# PureRingMod.net
KiCad netlist of a schematic drawn in EAGLE
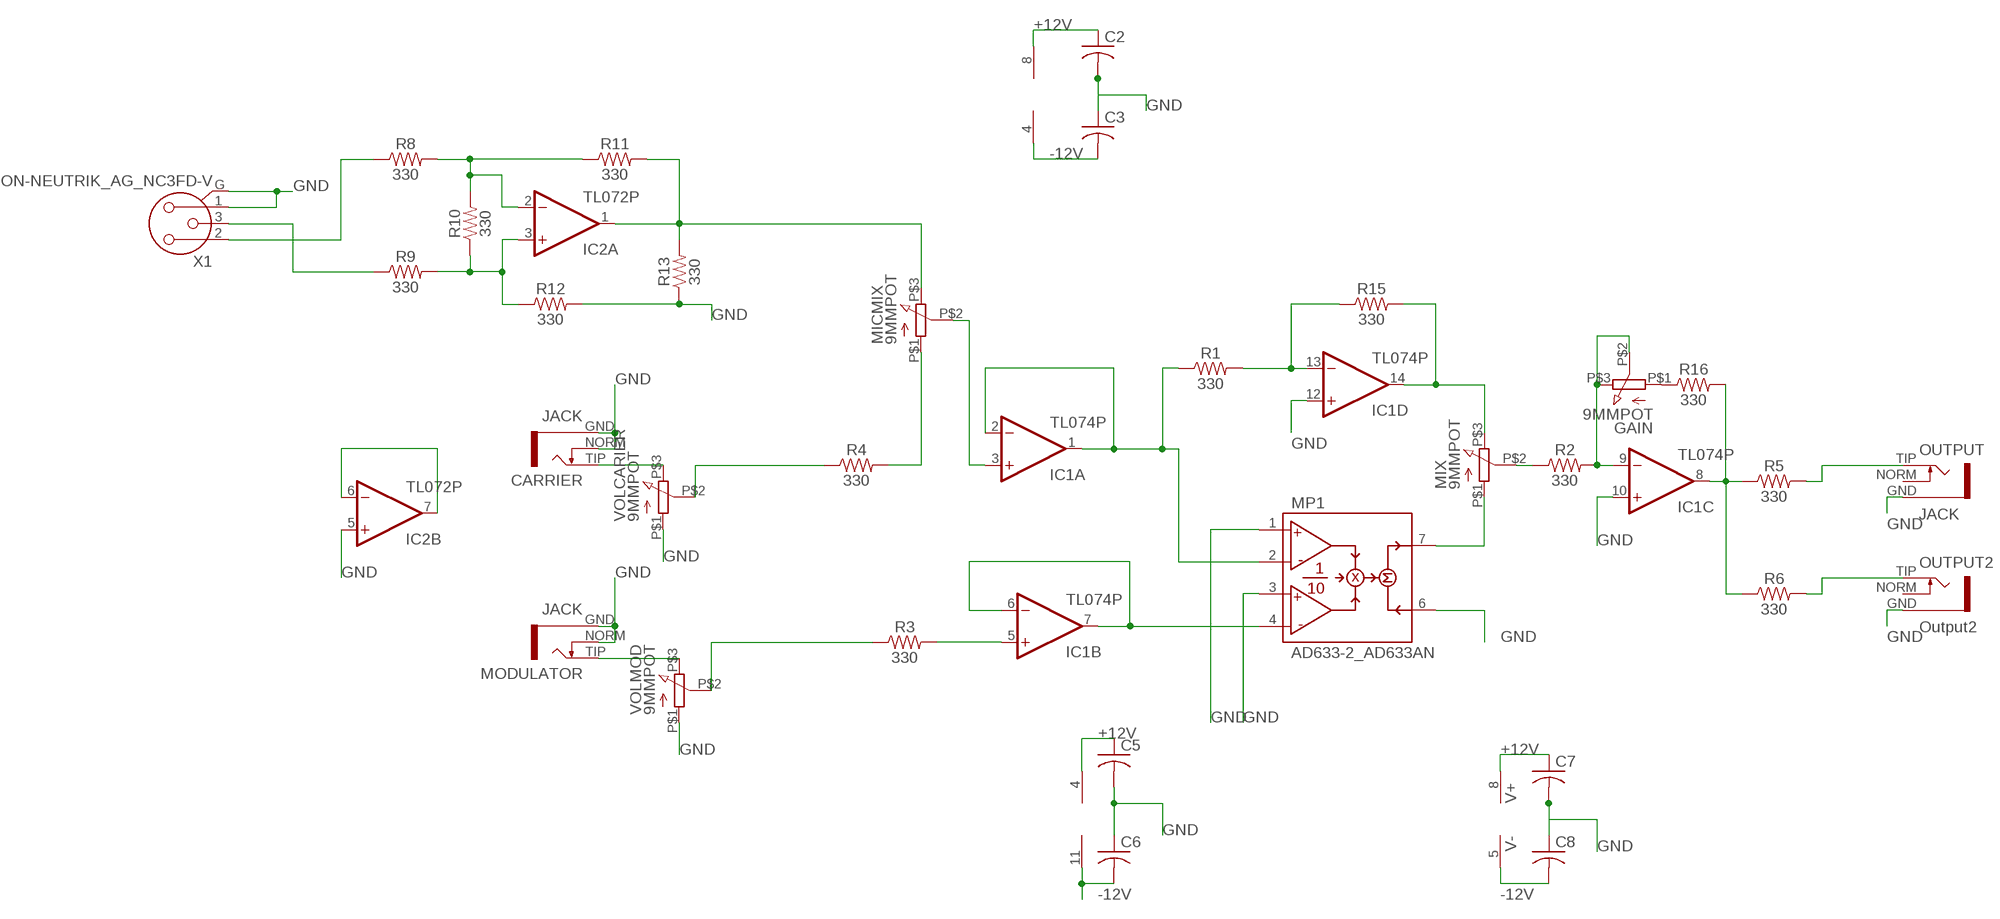
[diagram p0: schematic, sheet 1]
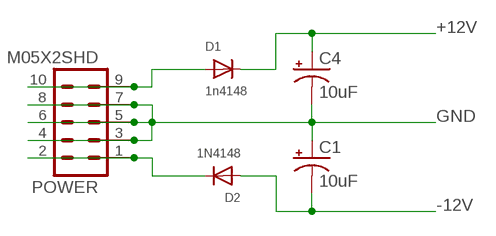
[diagram p1: schematic, sheet 2]

(export (version "E")
  (design (tool "Eeschema 10.0.6"))
  (components
    (comp (ref "C1")
      (value "10uF")
      (footprint "eagle-import:CPOL-RADIAL-2.5MM-5MM")
      (libsource (lib "eagle-import") (part "10UF-POLAR-RADIAL-2.5MM-25V-20%"))
    )
    (comp (ref "C4")
      (value "10uF")
      (footprint "eagle-import:CPOL-RADIAL-2.5MM-5MM")
      (libsource (lib "eagle-import") (part "10UF-POLAR-RADIAL-2.5MM-25V-20%"))
    )
    (comp (ref "D1")
      (value "1n4148")
      (footprint "eagle-import:DO-1N4148")
      (libsource (lib "eagle-import") (part "DIODEDO-1N4148"))
    )
    (comp (ref "D2")
      (value "1N4148")
      (footprint "eagle-import:DO-1N4148")
      (libsource (lib "eagle-import") (part "DIODEDO-1N4148"))
    )
    (comp (ref "POWER")
      (value "M05X2SHD")
      (footprint "eagle-import:2X5-SHROUDED")
      (libsource (lib "eagle-import") (part "M05X2SHD"))
    )
    (comp (ref "C2")
      (value "CAPACITOR-US050-025X075")
      (footprint "eagle-import:C050-025X075")
      (libsource (lib "eagle-import") (part "CAPACITOR-US050-025X075"))
    )
    (comp (ref "C3")
      (value "CAPACITOR-US050-025X075")
      (footprint "eagle-import:C050-025X075")
      (libsource (lib "eagle-import") (part "CAPACITOR-US050-025X075"))
    )
    (comp (ref "C5")
      (value "CAPACITOR-US050-025X075")
      (footprint "eagle-import:C050-025X075")
      (libsource (lib "eagle-import") (part "CAPACITOR-US050-025X075"))
    )
    (comp (ref "C6")
      (value "CAPACITOR-US050-025X075")
      (footprint "eagle-import:C050-025X075")
      (libsource (lib "eagle-import") (part "CAPACITOR-US050-025X075"))
    )
    (comp (ref "C7")
      (value "CAPACITOR-US050-025X075")
      (footprint "eagle-import:C050-025X075")
      (libsource (lib "eagle-import") (part "CAPACITOR-US050-025X075"))
    )
    (comp (ref "C8")
      (value "CAPACITOR-US050-025X075")
      (footprint "eagle-import:C050-025X075")
      (libsource (lib "eagle-import") (part "CAPACITOR-US050-025X075"))
    )
    (comp (ref "CARRIER")
      (value "JACK")
      (footprint "eagle-import:JACK")
      (libsource (lib "eagle-import") (part "JACK"))
    )
    (comp (ref "GAIN")
      (value "9MMPOT")
      (footprint "eagle-import:POT")
      (libsource (lib "eagle-import") (part "9MMPOT"))
    )
    (comp (ref "IC1")
      (value "TL074P")
      (footprint "eagle-import:DIL14")
      (libsource (lib "eagle-import") (part "TL074P"))
    )
    (comp (ref "IC2")
      (value "TL072P")
      (footprint "eagle-import:DIL08")
      (libsource (lib "eagle-import") (part "TL072P"))
    )
    (comp (ref "MICMIX")
      (value "9MMPOT")
      (footprint "eagle-import:POT")
      (libsource (lib "eagle-import") (part "9MMPOT"))
    )
    (comp (ref "MIX")
      (value "9MMPOT")
      (footprint "eagle-import:POT")
      (libsource (lib "eagle-import") (part "9MMPOT"))
    )
    (comp (ref "MODULATOR")
      (value "JACK")
      (footprint "eagle-import:JACK")
      (libsource (lib "eagle-import") (part "JACK"))
    )
    (comp (ref "MP1")
      (value "AD633-2_AD633AN")
      (footprint "eagle-import:AD633-2_DIL08")
      (libsource (lib "eagle-import") (part "AD633-2_AD633NA"))
    )
    (comp (ref "OUTPUT")
      (value "JACK")
      (footprint "eagle-import:JACK")
      (libsource (lib "eagle-import") (part "JACK"))
    )
    (comp (ref "OUTPUT2")
      (value "Output2")
      (footprint "eagle-import:JACK")
      (libsource (lib "eagle-import") (part "JACK"))
    )
    (comp (ref "R1")
      (value "330")
      (footprint "eagle-import:AXIAL-0.3")
      (libsource (lib "eagle-import") (part "330OHM-HORIZ-1/10W-5%"))
    )
    (comp (ref "R2")
      (value "330")
      (footprint "eagle-import:AXIAL-0.3")
      (libsource (lib "eagle-import") (part "330OHM-HORIZ-1/10W-5%"))
    )
    (comp (ref "R3")
      (value "330")
      (footprint "eagle-import:AXIAL-0.3")
      (libsource (lib "eagle-import") (part "330OHM-HORIZ-1/10W-5%"))
    )
    (comp (ref "R4")
      (value "330")
      (footprint "eagle-import:AXIAL-0.3")
      (libsource (lib "eagle-import") (part "330OHM-HORIZ-1/10W-5%"))
    )
    (comp (ref "R5")
      (value "330")
      (footprint "eagle-import:AXIAL-0.3")
      (libsource (lib "eagle-import") (part "330OHM-HORIZ-1/10W-5%"))
    )
    (comp (ref "R6")
      (value "330")
      (footprint "eagle-import:AXIAL-0.3")
      (libsource (lib "eagle-import") (part "330OHM-HORIZ-1/10W-5%"))
    )
    (comp (ref "R8")
      (value "330")
      (footprint "eagle-import:AXIAL-0.3")
      (libsource (lib "eagle-import") (part "330OHM-HORIZ-1/10W-5%"))
    )
    (comp (ref "R9")
      (value "330")
      (footprint "eagle-import:AXIAL-0.3")
      (libsource (lib "eagle-import") (part "330OHM-HORIZ-1/10W-5%"))
    )
    (comp (ref "R10")
      (value "330")
      (footprint "eagle-import:AXIAL-0.3")
      (libsource (lib "eagle-import") (part "330OHM-HORIZ-1/10W-5%"))
    )
    (comp (ref "R11")
      (value "330")
      (footprint "eagle-import:AXIAL-0.3")
      (libsource (lib "eagle-import") (part "330OHM-HORIZ-1/10W-5%"))
    )
    (comp (ref "R12")
      (value "330")
      (footprint "eagle-import:AXIAL-0.3")
      (libsource (lib "eagle-import") (part "330OHM-HORIZ-1/10W-5%"))
    )
    (comp (ref "R13")
      (value "330")
      (footprint "eagle-import:AXIAL-0.3")
      (libsource (lib "eagle-import") (part "330OHM-HORIZ-1/10W-5%"))
    )
    (comp (ref "R15")
      (value "330")
      (footprint "eagle-import:AXIAL-0.3")
      (libsource (lib "eagle-import") (part "330OHM-HORIZ-1/10W-5%"))
    )
    (comp (ref "R16")
      (value "330")
      (footprint "eagle-import:AXIAL-0.3")
      (libsource (lib "eagle-import") (part "330OHM-HORIZ-1/10W-5%"))
    )
    (comp (ref "VOLCARIER")
      (value "9MMPOT")
      (footprint "eagle-import:POT")
      (libsource (lib "eagle-import") (part "9MMPOT"))
    )
    (comp (ref "VOLMOD")
      (value "9MMPOT")
      (footprint "eagle-import:POT")
      (libsource (lib "eagle-import") (part "9MMPOT"))
    )
    (comp (ref "X1")
      (value "CON-NEUTRIK_AG_NC3FD-V")
      (footprint "eagle-import:CON-NEUTRIK_AG_NC3FD-V")
      (fields (field (name "MF") "FARNELL") (field (name "MPN") "NC3FDV") (field (name "RS-PART") "448-244"))
      (libsource (lib "eagle-import") (part "CON-NEUTRIK_AG_NC3FD-V"))
    )
  )
  (nets
    (net (code "1") (name "+12V") (class "Default")
      (node (ref "C2") (pin "1") (pinfunction "1_1") (pintype "passive"))
      (node (ref "C4") (pin "1") (pinfunction "+_1") (pintype "passive"))
      (node (ref "C5") (pin "1") (pinfunction "1_1") (pintype "passive"))
      (node (ref "C7") (pin "1") (pinfunction "1_1") (pintype "passive"))
      (node (ref "D1") (pin "C") (pinfunction "C_C") (pintype "passive"))
      (node (ref "IC1") (pin "4") (pinfunction "V+_4") (pintype "power_in"))
      (node (ref "IC2") (pin "8") (pinfunction "V+_8") (pintype "power_in"))
      (node (ref "MP1") (pin "8") (pinfunction "V+_8") (pintype "power_in"))
    )
    (net (code "2") (name "-12V") (class "Default")
      (node (ref "C1") (pin "2") (pinfunction "-_2") (pintype "passive"))
      (node (ref "C3") (pin "2") (pinfunction "2_2") (pintype "passive"))
      (node (ref "C6") (pin "2") (pinfunction "2_2") (pintype "passive"))
      (node (ref "C8") (pin "2") (pinfunction "2_2") (pintype "passive"))
      (node (ref "D2") (pin "A") (pinfunction "A_A") (pintype "passive"))
      (node (ref "IC1") (pin "11") (pinfunction "V-_11") (pintype "power_in"))
      (node (ref "IC2") (pin "4") (pinfunction "V-_4") (pintype "power_in"))
      (node (ref "MP1") (pin "5") (pinfunction "V-_5") (pintype "power_in"))
    )
    (net (code "3") (name "GND") (class "Default")
      (node (ref "C1") (pin "1") (pinfunction "+_1") (pintype "passive"))
      (node (ref "C2") (pin "2") (pinfunction "2_2") (pintype "passive"))
      (node (ref "C3") (pin "1") (pinfunction "1_1") (pintype "passive"))
      (node (ref "C4") (pin "2") (pinfunction "-_2") (pintype "passive"))
      (node (ref "C5") (pin "2") (pinfunction "2_2") (pintype "passive"))
      (node (ref "C6") (pin "1") (pinfunction "1_1") (pintype "passive"))
      (node (ref "C7") (pin "2") (pinfunction "2_2") (pintype "passive"))
      (node (ref "C8") (pin "1") (pinfunction "1_1") (pintype "passive"))
      (node (ref "CARRIER") (pin "GND") (pinfunction "GND_GND") (pintype "passive"))
      (node (ref "CARRIER") (pin "NORM") (pinfunction "NORM_NORM") (pintype "passive"))
      (node (ref "IC1") (pin "10") (pinfunction "+IN_10") (pintype "input"))
      (node (ref "IC1") (pin "12") (pinfunction "+IN_12") (pintype "input"))
      (node (ref "IC2") (pin "5") (pinfunction "+IN_5") (pintype "input"))
      (node (ref "MODULATOR") (pin "GND") (pinfunction "GND_GND") (pintype "passive"))
      (node (ref "MODULATOR") (pin "NORM") (pinfunction "NORM_NORM") (pintype "passive"))
      (node (ref "MP1") (pin "1") (pinfunction "X1_1") (pintype "input"))
      (node (ref "MP1") (pin "3") (pinfunction "Y1_3") (pintype "input"))
      (node (ref "MP1") (pin "6") (pinfunction "Z_6") (pintype "input"))
      (node (ref "OUTPUT") (pin "GND") (pinfunction "GND_GND") (pintype "passive"))
      (node (ref "OUTPUT2") (pin "GND") (pinfunction "GND_GND") (pintype "passive"))
      (node (ref "POWER") (pin "3") (pinfunction "3_3") (pintype "passive"))
      (node (ref "POWER") (pin "4") (pinfunction "4_4") (pintype "passive"))
      (node (ref "POWER") (pin "5") (pinfunction "5_5") (pintype "passive"))
      (node (ref "POWER") (pin "6") (pinfunction "6_6") (pintype "passive"))
      (node (ref "POWER") (pin "7") (pinfunction "7_7") (pintype "passive"))
      (node (ref "POWER") (pin "8") (pinfunction "8_8") (pintype "passive"))
      (node (ref "R12") (pin "P$2") (pinfunction "2_P$2") (pintype "passive"))
      (node (ref "R13") (pin "P$1") (pinfunction "1_P$1") (pintype "passive"))
      (node (ref "VOLCARIER") (pin "P$1") (pinfunction "1_P$1") (pintype "passive"))
      (node (ref "VOLMOD") (pin "P$1") (pinfunction "1_P$1") (pintype "passive"))
      (node (ref "X1") (pin "1") (pinfunction "2_1") (pintype "passive"))
      (node (ref "X1") (pin "G") (pinfunction "G_G") (pintype "passive"))
    )
    (net (code "4") (name "Net-(D1-PadA)") (class "Default")
      (node (ref "D1") (pin "A") (pinfunction "A_A") (pintype "passive"))
      (node (ref "POWER") (pin "10") (pinfunction "10_10") (pintype "passive"))
      (node (ref "POWER") (pin "9") (pinfunction "9_9") (pintype "passive"))
    )
    (net (code "5") (name "Net-(D2-PadC)") (class "Default")
      (node (ref "D2") (pin "C") (pinfunction "C_C") (pintype "passive"))
      (node (ref "POWER") (pin "1") (pinfunction "1_1") (pintype "passive"))
      (node (ref "POWER") (pin "2") (pinfunction "2_2") (pintype "passive"))
    )
    (net (code "6") (name "Net-(GAIN-1)") (class "Default")
      (node (ref "GAIN") (pin "P$1") (pinfunction "1_P$1") (pintype "passive"))
      (node (ref "R16") (pin "P$1") (pinfunction "1_P$1") (pintype "passive"))
    )
    (net (code "7") (name "Net-(GAIN-2)") (class "Default")
      (node (ref "GAIN") (pin "P$2") (pinfunction "2_P$2") (pintype "passive"))
      (node (ref "GAIN") (pin "P$3") (pinfunction "3_P$3") (pintype "passive"))
      (node (ref "IC1") (pin "9") (pinfunction "-IN_9") (pintype "input"))
      (node (ref "R2") (pin "P$2") (pinfunction "2_P$2") (pintype "passive"))
    )
    (net (code "8") (name "Net-(IC1A-+IN)") (class "Default")
      (node (ref "IC1") (pin "3") (pinfunction "+IN_3") (pintype "input"))
      (node (ref "MICMIX") (pin "P$2") (pinfunction "2_P$2") (pintype "passive"))
    )
    (net (code "9") (name "Net-(IC1A--IN)") (class "Default")
      (node (ref "IC1") (pin "1") (pinfunction "OUT_1") (pintype "output"))
      (node (ref "IC1") (pin "2") (pinfunction "-IN_2") (pintype "input"))
      (node (ref "MP1") (pin "2") (pinfunction "X2_2") (pintype "input"))
      (node (ref "R1") (pin "P$1") (pinfunction "1_P$1") (pintype "passive"))
    )
    (net (code "10") (name "Net-(IC1B-+IN)") (class "Default")
      (node (ref "IC1") (pin "5") (pinfunction "+IN_5") (pintype "input"))
      (node (ref "R3") (pin "P$2") (pinfunction "2_P$2") (pintype "passive"))
    )
    (net (code "11") (name "Net-(IC1B--IN)") (class "Default")
      (node (ref "IC1") (pin "6") (pinfunction "-IN_6") (pintype "input"))
      (node (ref "IC1") (pin "7") (pinfunction "OUT_7") (pintype "output"))
      (node (ref "MP1") (pin "4") (pinfunction "Y2_4") (pintype "input"))
    )
    (net (code "12") (name "Net-(IC1C-OUT)") (class "Default")
      (node (ref "IC1") (pin "8") (pinfunction "OUT_8") (pintype "output"))
      (node (ref "R16") (pin "P$2") (pinfunction "2_P$2") (pintype "passive"))
      (node (ref "R5") (pin "P$1") (pinfunction "1_P$1") (pintype "passive"))
      (node (ref "R6") (pin "P$1") (pinfunction "1_P$1") (pintype "passive"))
    )
    (net (code "13") (name "Net-(IC1D--IN)") (class "Default")
      (node (ref "IC1") (pin "13") (pinfunction "-IN_13") (pintype "input"))
      (node (ref "R1") (pin "P$2") (pinfunction "2_P$2") (pintype "passive"))
      (node (ref "R15") (pin "P$1") (pinfunction "1_P$1") (pintype "passive"))
    )
    (net (code "14") (name "Net-(IC1D-OUT)") (class "Default")
      (node (ref "IC1") (pin "14") (pinfunction "OUT_14") (pintype "output"))
      (node (ref "MIX") (pin "P$3") (pinfunction "3_P$3") (pintype "passive"))
      (node (ref "R15") (pin "P$2") (pinfunction "2_P$2") (pintype "passive"))
    )
    (net (code "15") (name "Net-(IC2A-+IN)") (class "Default")
      (node (ref "IC2") (pin "3") (pinfunction "+IN_3") (pintype "input"))
      (node (ref "R10") (pin "P$1") (pinfunction "1_P$1") (pintype "passive"))
      (node (ref "R12") (pin "P$1") (pinfunction "1_P$1") (pintype "passive"))
      (node (ref "R9") (pin "P$2") (pinfunction "2_P$2") (pintype "passive"))
    )
    (net (code "16") (name "Net-(IC2A--IN)") (class "Default")
      (node (ref "IC2") (pin "2") (pinfunction "-IN_2") (pintype "input"))
      (node (ref "R10") (pin "P$2") (pinfunction "2_P$2") (pintype "passive"))
      (node (ref "R11") (pin "P$1") (pinfunction "1_P$1") (pintype "passive"))
      (node (ref "R8") (pin "P$2") (pinfunction "2_P$2") (pintype "passive"))
    )
    (net (code "17") (name "Net-(IC2A-OUT)") (class "Default")
      (node (ref "IC2") (pin "1") (pinfunction "OUT_1") (pintype "output"))
      (node (ref "MICMIX") (pin "P$3") (pinfunction "3_P$3") (pintype "passive"))
      (node (ref "R11") (pin "P$2") (pinfunction "2_P$2") (pintype "passive"))
      (node (ref "R13") (pin "P$2") (pinfunction "2_P$2") (pintype "passive"))
    )
    (net (code "18") (name "Net-(IC2B--IN)") (class "Default")
      (node (ref "IC2") (pin "6") (pinfunction "-IN_6") (pintype "input"))
      (node (ref "IC2") (pin "7") (pinfunction "OUT_7") (pintype "output"))
    )
    (net (code "19") (name "Net-(MICMIX-1)") (class "Default")
      (node (ref "MICMIX") (pin "P$1") (pinfunction "1_P$1") (pintype "passive"))
      (node (ref "R4") (pin "P$2") (pinfunction "2_P$2") (pintype "passive"))
    )
    (net (code "20") (name "Net-(MIX-1)") (class "Default")
      (node (ref "MIX") (pin "P$1") (pinfunction "1_P$1") (pintype "passive"))
      (node (ref "MP1") (pin "7") (pinfunction "W_7") (pintype "output"))
    )
    (net (code "21") (name "Net-(MIX-2)") (class "Default")
      (node (ref "MIX") (pin "P$2") (pinfunction "2_P$2") (pintype "passive"))
      (node (ref "R2") (pin "P$1") (pinfunction "1_P$1") (pintype "passive"))
    )
    (net (code "22") (name "Net-(R3-1)") (class "Default")
      (node (ref "R3") (pin "P$1") (pinfunction "1_P$1") (pintype "passive"))
      (node (ref "VOLMOD") (pin "P$2") (pinfunction "2_P$2") (pintype "passive"))
    )
    (net (code "23") (name "Net-(R4-1)") (class "Default")
      (node (ref "R4") (pin "P$1") (pinfunction "1_P$1") (pintype "passive"))
      (node (ref "VOLCARIER") (pin "P$2") (pinfunction "2_P$2") (pintype "passive"))
    )
    (net (code "24") (name "Net-(R5-2)") (class "Default")
      (node (ref "OUTPUT") (pin "TIP") (pinfunction "TIP_TIP") (pintype "passive"))
      (node (ref "R5") (pin "P$2") (pinfunction "2_P$2") (pintype "passive"))
    )
    (net (code "25") (name "Net-(R6-2)") (class "Default")
      (node (ref "OUTPUT2") (pin "TIP") (pinfunction "TIP_TIP") (pintype "passive"))
      (node (ref "R6") (pin "P$2") (pinfunction "2_P$2") (pintype "passive"))
    )
    (net (code "26") (name "Net-(R8-1)") (class "Default")
      (node (ref "R8") (pin "P$1") (pinfunction "1_P$1") (pintype "passive"))
      (node (ref "X1") (pin "2") (pinfunction "1_2") (pintype "passive"))
    )
    (net (code "27") (name "Net-(R9-1)") (class "Default")
      (node (ref "R9") (pin "P$1") (pinfunction "1_P$1") (pintype "passive"))
      (node (ref "X1") (pin "3") (pinfunction "3_3") (pintype "passive"))
    )
    (net (code "28") (name "Net-(VOLCARIER-3)") (class "Default")
      (node (ref "CARRIER") (pin "TIP") (pinfunction "TIP_TIP") (pintype "passive"))
      (node (ref "VOLCARIER") (pin "P$3") (pinfunction "3_P$3") (pintype "passive"))
    )
    (net (code "29") (name "Net-(VOLMOD-3)") (class "Default")
      (node (ref "MODULATOR") (pin "TIP") (pinfunction "TIP_TIP") (pintype "passive"))
      (node (ref "VOLMOD") (pin "P$3") (pinfunction "3_P$3") (pintype "passive"))
    )
    (net (code "30") (name "unconnected-(OUTPUT-PadNORM)") (class "Default")
      (node (ref "OUTPUT") (pin "NORM") (pinfunction "NORM_NORM") (pintype "passive"))
    )
    (net (code "31") (name "unconnected-(OUTPUT2-PadNORM)") (class "Default")
      (node (ref "OUTPUT2") (pin "NORM") (pinfunction "NORM_NORM") (pintype "passive"))
    )
  )
)
